# WiFi.net
KiCad netlist of a schematic drawn in Altium Designer
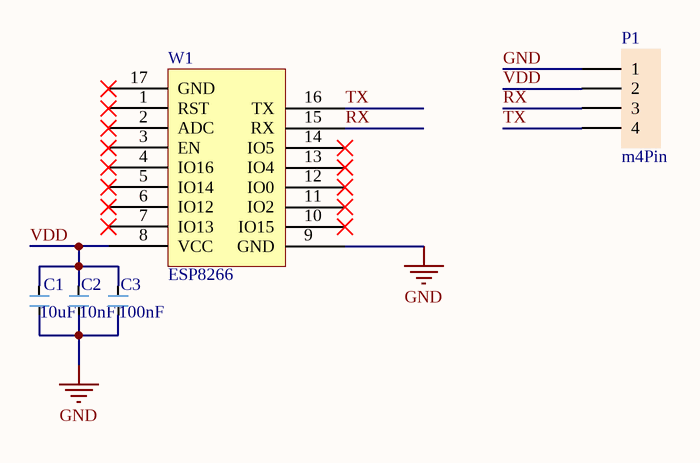
[diagram p0: WiFi.SchDoc]

(export (version "E")
  (design (tool "Eeschema 10.0.6"))
  (components
    (comp (ref "C1")
      (value "10uF")
      (footprint "C0603")
      (description "陶瓷电容")
      (libsource (lib "DemoSchlib") (part "C0603"))
    )
    (comp (ref "C2")
      (value "10nF")
      (footprint "C0603")
      (description "陶瓷电容")
      (libsource (lib "DemoSchlib") (part "C0603"))
    )
    (comp (ref "C3")
      (value "100nF")
      (footprint "C0603")
      (description "陶瓷电容")
      (libsource (lib "DemoSchlib") (part "C0603"))
    )
    (comp (ref "P1")
      (value "m4Pin")
      (footprint "4x1 header")
      (description "1x4pin 1.27mm")
      (libsource (lib "DemoSchlib") (part "m4Pin"))
    )
    (comp (ref "W1") (value "ESP8266") (footprint "ESP-12S") (libsource (lib "DemoSchlib") (part "ESP8266")))
  )
  (nets
    (net (code "1") (name "/RX") (class "Default")
      (node (ref "P1") (pin "3") (pinfunction "3_3") (pintype "passive"))
      (node (ref "W1") (pin "15") (pinfunction "RX_15") (pintype "passive"))
    )
    (net (code "2") (name "/TX") (class "Default")
      (node (ref "P1") (pin "4") (pinfunction "4_4") (pintype "passive"))
      (node (ref "W1") (pin "16") (pinfunction "TX_16") (pintype "passive"))
    )
    (net (code "3") (name "/VDD") (class "Default")
      (node (ref "C1") (pin "2") (pintype "passive"))
      (node (ref "C2") (pin "2") (pintype "passive"))
      (node (ref "C3") (pin "2") (pintype "passive"))
      (node (ref "P1") (pin "2") (pinfunction "2_2") (pintype "passive"))
      (node (ref "W1") (pin "8") (pinfunction "VCC_8") (pintype "passive"))
    )
    (net (code "4") (name "GND") (class "Default")
      (node (ref "C1") (pin "1") (pintype "passive"))
      (node (ref "C2") (pin "1") (pintype "passive"))
      (node (ref "C3") (pin "1") (pintype "passive"))
      (node (ref "P1") (pin "1") (pinfunction "1_1") (pintype "passive"))
      (node (ref "W1") (pin "9") (pinfunction "GND_9") (pintype "passive"))
    )
    (net (code "5") (name "unconnected-(W1-ADC-Pad2)") (class "Default")
      (node (ref "W1") (pin "2") (pinfunction "ADC_2") (pintype "passive+no_connect"))
    )
    (net (code "6") (name "unconnected-(W1-EN-Pad3)") (class "Default")
      (node (ref "W1") (pin "3") (pinfunction "EN_3") (pintype "passive+no_connect"))
    )
    (net (code "7") (name "unconnected-(W1-GND-Pad17)") (class "Default")
      (node (ref "W1") (pin "17") (pinfunction "GND_17") (pintype "passive+no_connect"))
    )
    (net (code "8") (name "unconnected-(W1-IO0-Pad12)") (class "Default")
      (node (ref "W1") (pin "12") (pinfunction "IO0_12") (pintype "passive+no_connect"))
    )
    (net (code "9") (name "unconnected-(W1-IO2-Pad11)") (class "Default")
      (node (ref "W1") (pin "11") (pinfunction "IO2_11") (pintype "passive+no_connect"))
    )
    (net (code "10") (name "unconnected-(W1-IO4-Pad13)") (class "Default")
      (node (ref "W1") (pin "13") (pinfunction "IO4_13") (pintype "passive+no_connect"))
    )
    (net (code "11") (name "unconnected-(W1-IO5-Pad14)") (class "Default")
      (node (ref "W1") (pin "14") (pinfunction "IO5_14") (pintype "passive+no_connect"))
    )
    (net (code "12") (name "unconnected-(W1-IO12-Pad6)") (class "Default")
      (node (ref "W1") (pin "6") (pinfunction "IO12_6") (pintype "passive+no_connect"))
    )
    (net (code "13") (name "unconnected-(W1-IO13-Pad7)") (class "Default")
      (node (ref "W1") (pin "7") (pinfunction "IO13_7") (pintype "passive+no_connect"))
    )
    (net (code "14") (name "unconnected-(W1-IO14-Pad5)") (class "Default")
      (node (ref "W1") (pin "5") (pinfunction "IO14_5") (pintype "passive+no_connect"))
    )
    (net (code "15") (name "unconnected-(W1-IO15-Pad10)") (class "Default")
      (node (ref "W1") (pin "10") (pinfunction "IO15_10") (pintype "passive+no_connect"))
    )
    (net (code "16") (name "unconnected-(W1-IO16-Pad4)") (class "Default")
      (node (ref "W1") (pin "4") (pinfunction "IO16_4") (pintype "passive+no_connect"))
    )
    (net (code "17") (name "unconnected-(W1-RST-Pad1)") (class "Default")
      (node (ref "W1") (pin "1") (pinfunction "RST_1") (pintype "passive+no_connect"))
    )
  )
)
